# power.net
KiCad netlist of a schematic drawn in EAGLE
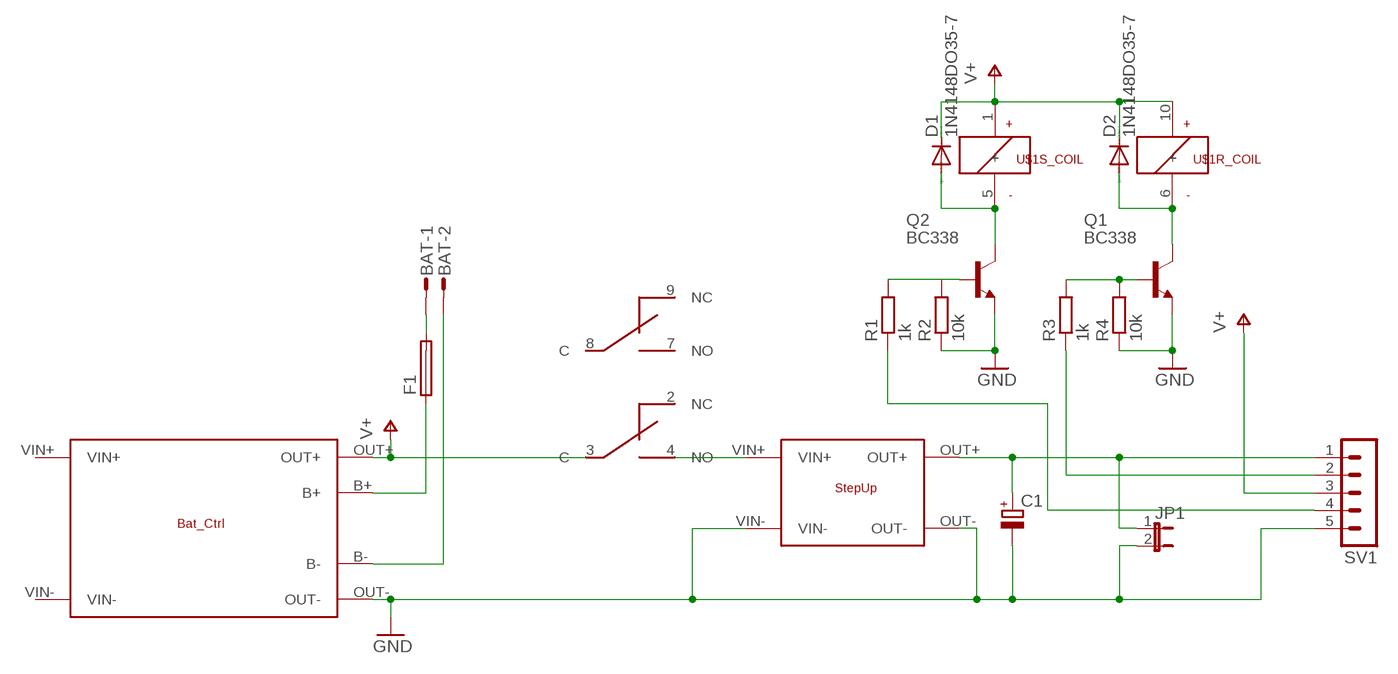
[diagram p0: schematic, sheet 1]

(export (version "E")
  (design (tool "Eeschema 10.0.6"))
  (components
    (comp (ref "BAT")
      (value "S02P")
      (footprint "eagle-import:S02P")
      (libsource (lib "eagle-import") (part "S02P"))
    )
    (comp (ref "C1")
      (value "CPOL-EUE3.5-8")
      (footprint "eagle-import:E3,5-8")
      (libsource (lib "eagle-import") (part "CPOL-EUE3.5-8"))
    )
    (comp (ref "D1")
      (value "1N4148DO35-7")
      (footprint "eagle-import:DO35-7")
      (libsource (lib "eagle-import") (part "1N4148DO35-7"))
    )
    (comp (ref "D2")
      (value "1N4148DO35-7")
      (footprint "eagle-import:DO35-7")
      (libsource (lib "eagle-import") (part "1N4148DO35-7"))
    )
    (comp (ref "F1")
      (value "SH22,5")
      (footprint "eagle-import:SH22,5")
      (fields (field (name "MF") "SCHURTER") (field (name "MPN") "0031.8201"))
      (libsource (lib "eagle-import") (part "SH22,5"))
    )
    (comp (ref "JP1")
      (value "JP1E")
      (footprint "eagle-import:JP1")
      (libsource (lib "eagle-import") (part "JP1E"))
    )
    (comp (ref "Q1")
      (value "BC338")
      (footprint "eagle-import:TO92-EBC")
      (libsource (lib "eagle-import") (part "BC338"))
    )
    (comp (ref "Q2")
      (value "BC338")
      (footprint "eagle-import:TO92-EBC")
      (libsource (lib "eagle-import") (part "BC338"))
    )
    (comp (ref "R1")
      (value "1k")
      (footprint "eagle-import:0204_7")
      (libsource (lib "eagle-import") (part "R-EU_0204/7"))
    )
    (comp (ref "R2")
      (value "10k")
      (footprint "eagle-import:M1206")
      (libsource (lib "eagle-import") (part "R-EU_M1206"))
    )
    (comp (ref "R3")
      (value "1k")
      (footprint "eagle-import:0204_7")
      (libsource (lib "eagle-import") (part "R-EU_0204/7"))
    )
    (comp (ref "R4")
      (value "10k")
      (footprint "eagle-import:M1206")
      (libsource (lib "eagle-import") (part "R-EU_M1206"))
    )
    (comp (ref "SV1")
      (value "MA05-1")
      (footprint "eagle-import:MA05-1")
      (libsource (lib "eagle-import") (part "MA05-1"))
    )
    (comp (ref "U$1")
      (value "EB2-4.5TNU")
      (footprint "eagle-import:10PIN_SMD_RELAY")
      (libsource (lib "eagle-import") (part "EB2-4.5TNU"))
    )
    (comp (ref "U$2")
      (value "STEP_UP")
      (footprint "eagle-import:STEP_UP")
      (libsource (lib "eagle-import") (part "STEP_UP"))
    )
    (comp (ref "U$3")
      (value "BAT_CTRL")
      (footprint "eagle-import:BAT_CONTR")
      (libsource (lib "eagle-import") (part "BAT_CTRL"))
    )
  )
  (nets
    (net (code "1") (name "GND") (class "Default")
      (node (ref "C1") (pin "-") (pinfunction "-_-") (pintype "passive"))
      (node (ref "JP1") (pin "2") (pinfunction "2_2") (pintype "passive"))
      (node (ref "Q1") (pin "E") (pinfunction "E_E") (pintype "passive"))
      (node (ref "Q2") (pin "E") (pinfunction "E_E") (pintype "passive"))
      (node (ref "R2") (pin "1") (pinfunction "1_1") (pintype "passive"))
      (node (ref "R4") (pin "1") (pinfunction "1_1") (pintype "passive"))
      (node (ref "SV1") (pin "5") (pinfunction "5_5") (pintype "passive"))
      (node (ref "U$2") (pin "OUT-") (pinfunction "OUT-_OUT-") (pintype "bidirectional"))
      (node (ref "U$2") (pin "VIN-") (pinfunction "VIN-_VIN-") (pintype "bidirectional"))
      (node (ref "U$3") (pin "OUT-") (pinfunction "OUT-_OUT-") (pintype "bidirectional"))
    )
    (net (code "2") (name "Net-(BATA-S)") (class "Default")
      (node (ref "BAT") (pin "1") (pinfunction "S_1") (pintype "passive"))
      (node (ref "F1") (pin "2") (pinfunction "2_2") (pintype "passive"))
    )
    (net (code "3") (name "Net-(BATB-S)") (class "Default")
      (node (ref "BAT") (pin "2") (pinfunction "S_2") (pintype "passive"))
      (node (ref "U$3") (pin "B-") (pinfunction "B-_B-") (pintype "bidirectional"))
    )
    (net (code "4") (name "Net-(C1-Pad+)") (class "Default")
      (node (ref "C1") (pin "+") (pinfunction "+_+") (pintype "passive"))
      (node (ref "JP1") (pin "1") (pinfunction "1_1") (pintype "passive"))
      (node (ref "SV1") (pin "1") (pinfunction "1_1") (pintype "passive"))
      (node (ref "U$2") (pin "OUT+") (pinfunction "OUT+_OUT+") (pintype "bidirectional"))
    )
    (net (code "5") (name "Net-(F1-Pad1)") (class "Default")
      (node (ref "F1") (pin "1") (pinfunction "1_1") (pintype "passive"))
      (node (ref "U$3") (pin "B+") (pinfunction "B+_B+") (pintype "bidirectional"))
    )
    (net (code "6") (name "Net-(Q1-PadB)") (class "Default")
      (node (ref "Q1") (pin "B") (pinfunction "B_B") (pintype "passive"))
      (node (ref "R3") (pin "2") (pinfunction "2_2") (pintype "passive"))
      (node (ref "R4") (pin "2") (pinfunction "2_2") (pintype "passive"))
    )
    (net (code "7") (name "Net-(Q2-PadB)") (class "Default")
      (node (ref "Q2") (pin "B") (pinfunction "B_B") (pintype "passive"))
      (node (ref "R1") (pin "2") (pinfunction "2_2") (pintype "passive"))
      (node (ref "R2") (pin "2") (pinfunction "2_2") (pintype "passive"))
    )
    (net (code "8") (name "Net-(R1-Pad1)") (class "Default")
      (node (ref "R1") (pin "1") (pinfunction "1_1") (pintype "passive"))
      (node (ref "SV1") (pin "4") (pinfunction "4_4") (pintype "passive"))
    )
    (net (code "9") (name "Net-(R3-Pad1)") (class "Default")
      (node (ref "R3") (pin "1") (pinfunction "1_1") (pintype "passive"))
      (node (ref "SV1") (pin "2") (pinfunction "2_2") (pintype "passive"))
    )
    (net (code "10") (name "Net-(U$1A--)") (class "Default")
      (node (ref "D2") (pin "A") (pinfunction "A_A") (pintype "passive"))
      (node (ref "Q1") (pin "C") (pinfunction "C_C") (pintype "passive"))
      (node (ref "U$1") (pin "6") (pinfunction "-_6") (pintype "bidirectional"))
    )
    (net (code "11") (name "Net-(U$1C-NO)") (class "Default")
      (node (ref "U$1") (pin "4") (pinfunction "NO_4") (pintype "bidirectional"))
      (node (ref "U$2") (pin "VIN+") (pinfunction "VIN+_VIN+") (pintype "bidirectional"))
    )
    (net (code "12") (name "Net-(U$1D--)") (class "Default")
      (node (ref "D1") (pin "A") (pinfunction "A_A") (pintype "passive"))
      (node (ref "Q2") (pin "C") (pinfunction "C_C") (pintype "passive"))
      (node (ref "U$1") (pin "5") (pinfunction "-_5") (pintype "bidirectional"))
    )
    (net (code "13") (name "V+") (class "Default")
      (node (ref "D1") (pin "C") (pinfunction "C_C") (pintype "passive"))
      (node (ref "D2") (pin "C") (pinfunction "C_C") (pintype "passive"))
      (node (ref "SV1") (pin "3") (pinfunction "3_3") (pintype "passive"))
      (node (ref "U$1") (pin "1") (pinfunction "+_1") (pintype "bidirectional"))
      (node (ref "U$1") (pin "10") (pinfunction "+_10") (pintype "bidirectional"))
      (node (ref "U$1") (pin "3") (pinfunction "C_3") (pintype "bidirectional"))
      (node (ref "U$3") (pin "OUT+") (pinfunction "OUT+_OUT+") (pintype "bidirectional"))
    )
    (net (code "14") (name "unconnected-(U$1B-C-Pad8)") (class "Default")
      (node (ref "U$1") (pin "8") (pinfunction "C_8") (pintype "bidirectional"))
    )
    (net (code "15") (name "unconnected-(U$1B-NC-Pad9)") (class "Default")
      (node (ref "U$1") (pin "9") (pinfunction "NC_9") (pintype "bidirectional"))
    )
    (net (code "16") (name "unconnected-(U$1B-NO-Pad7)") (class "Default")
      (node (ref "U$1") (pin "7") (pinfunction "NO_7") (pintype "bidirectional"))
    )
    (net (code "17") (name "unconnected-(U$1C-NC-Pad2)") (class "Default")
      (node (ref "U$1") (pin "2") (pinfunction "NC_2") (pintype "bidirectional"))
    )
    (net (code "18") (name "unconnected-(U$3-PadVIN+)") (class "Default")
      (node (ref "U$3") (pin "VIN+") (pinfunction "VIN+_VIN+") (pintype "bidirectional"))
    )
    (net (code "19") (name "unconnected-(U$3-PadVIN-)") (class "Default")
      (node (ref "U$3") (pin "VIN-") (pinfunction "VIN-_VIN-") (pintype "bidirectional"))
    )
  )
)
